# AntiAlias_Filter_Diff_Active.net
KiCad netlist of a schematic drawn in EAGLE
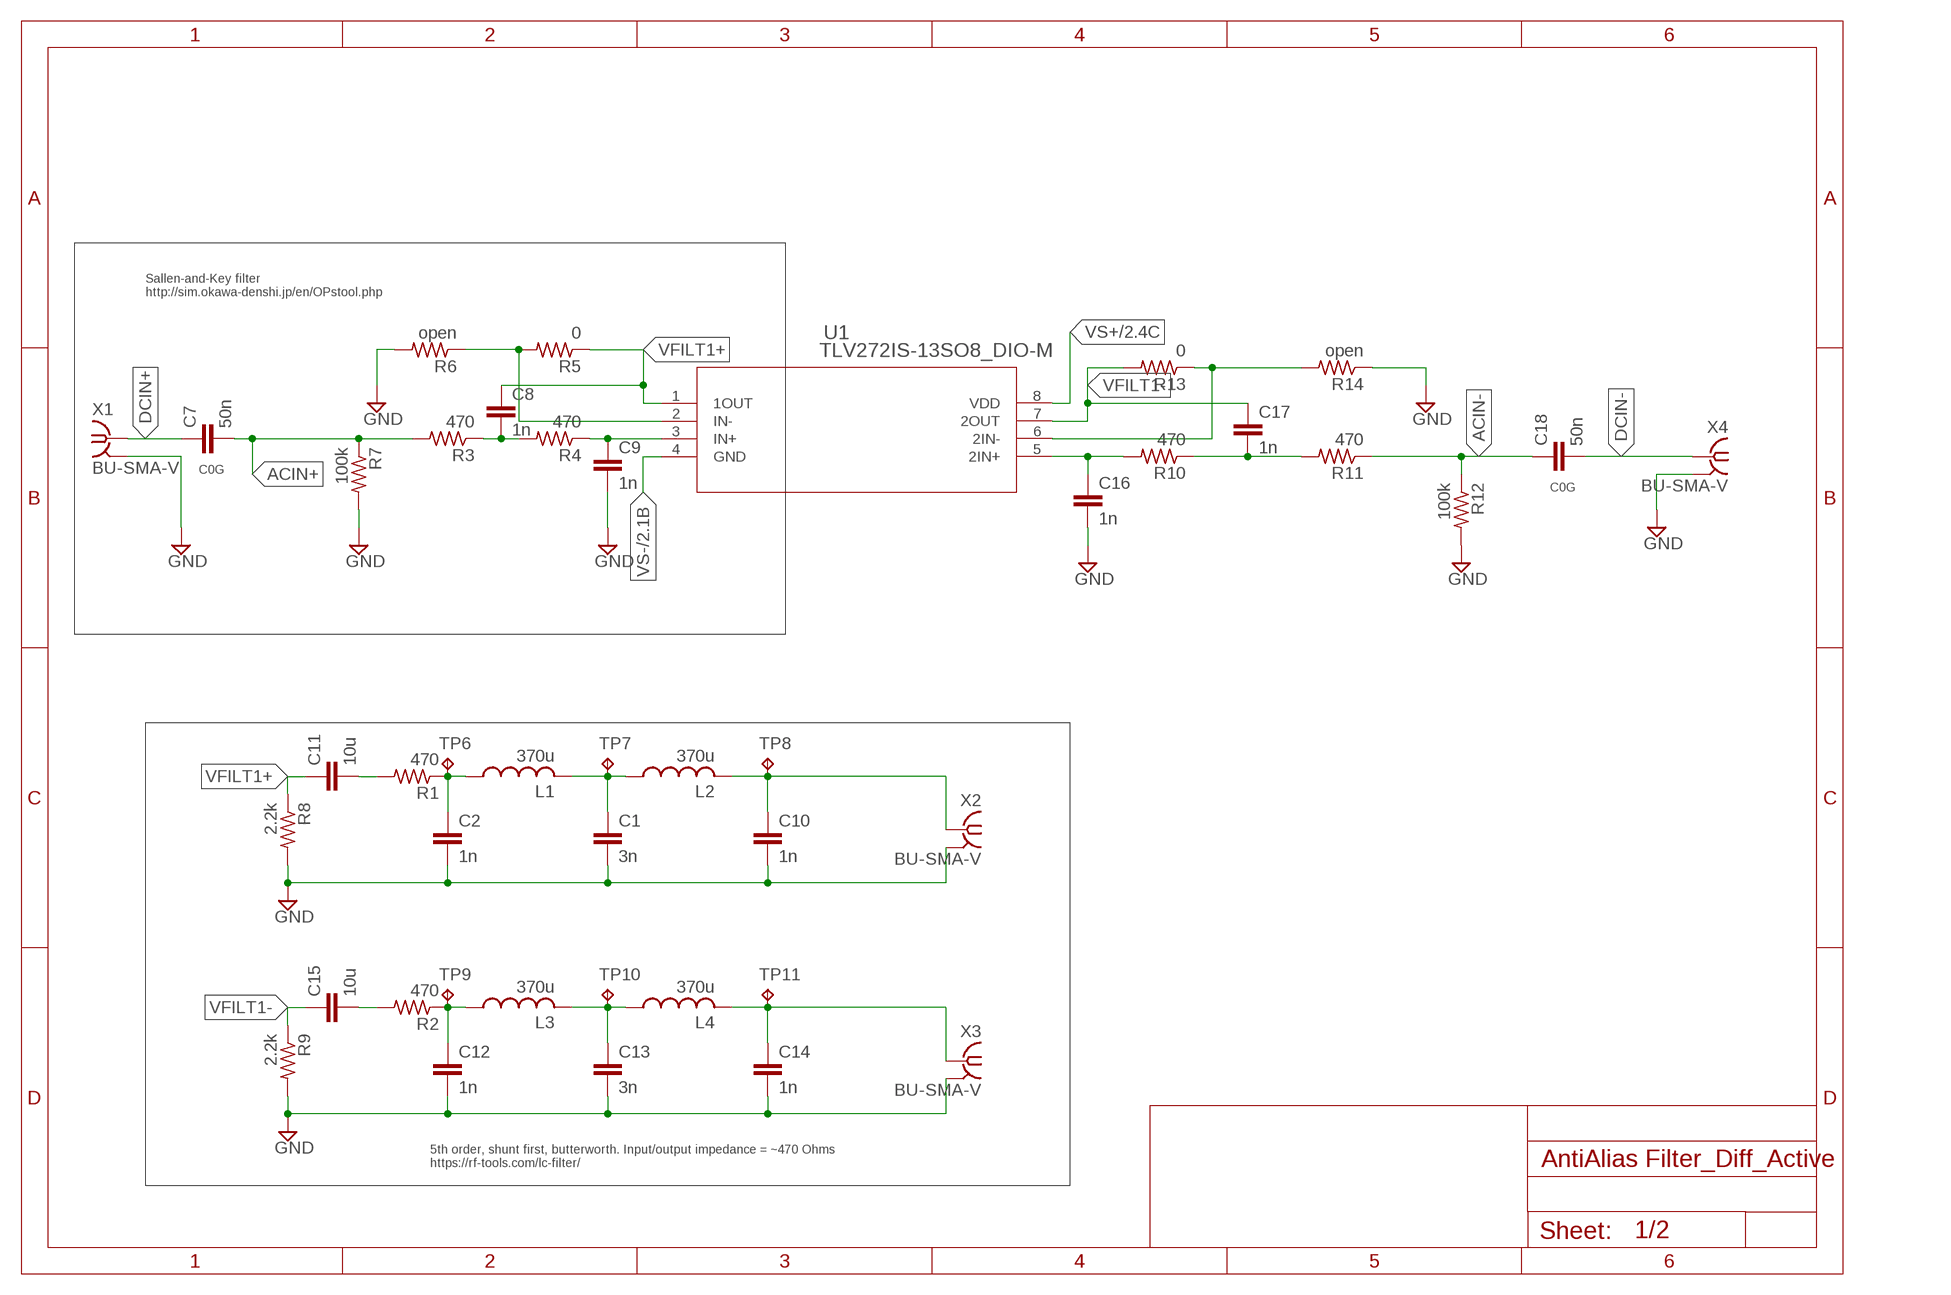
[diagram p0: schematic, sheet 1]
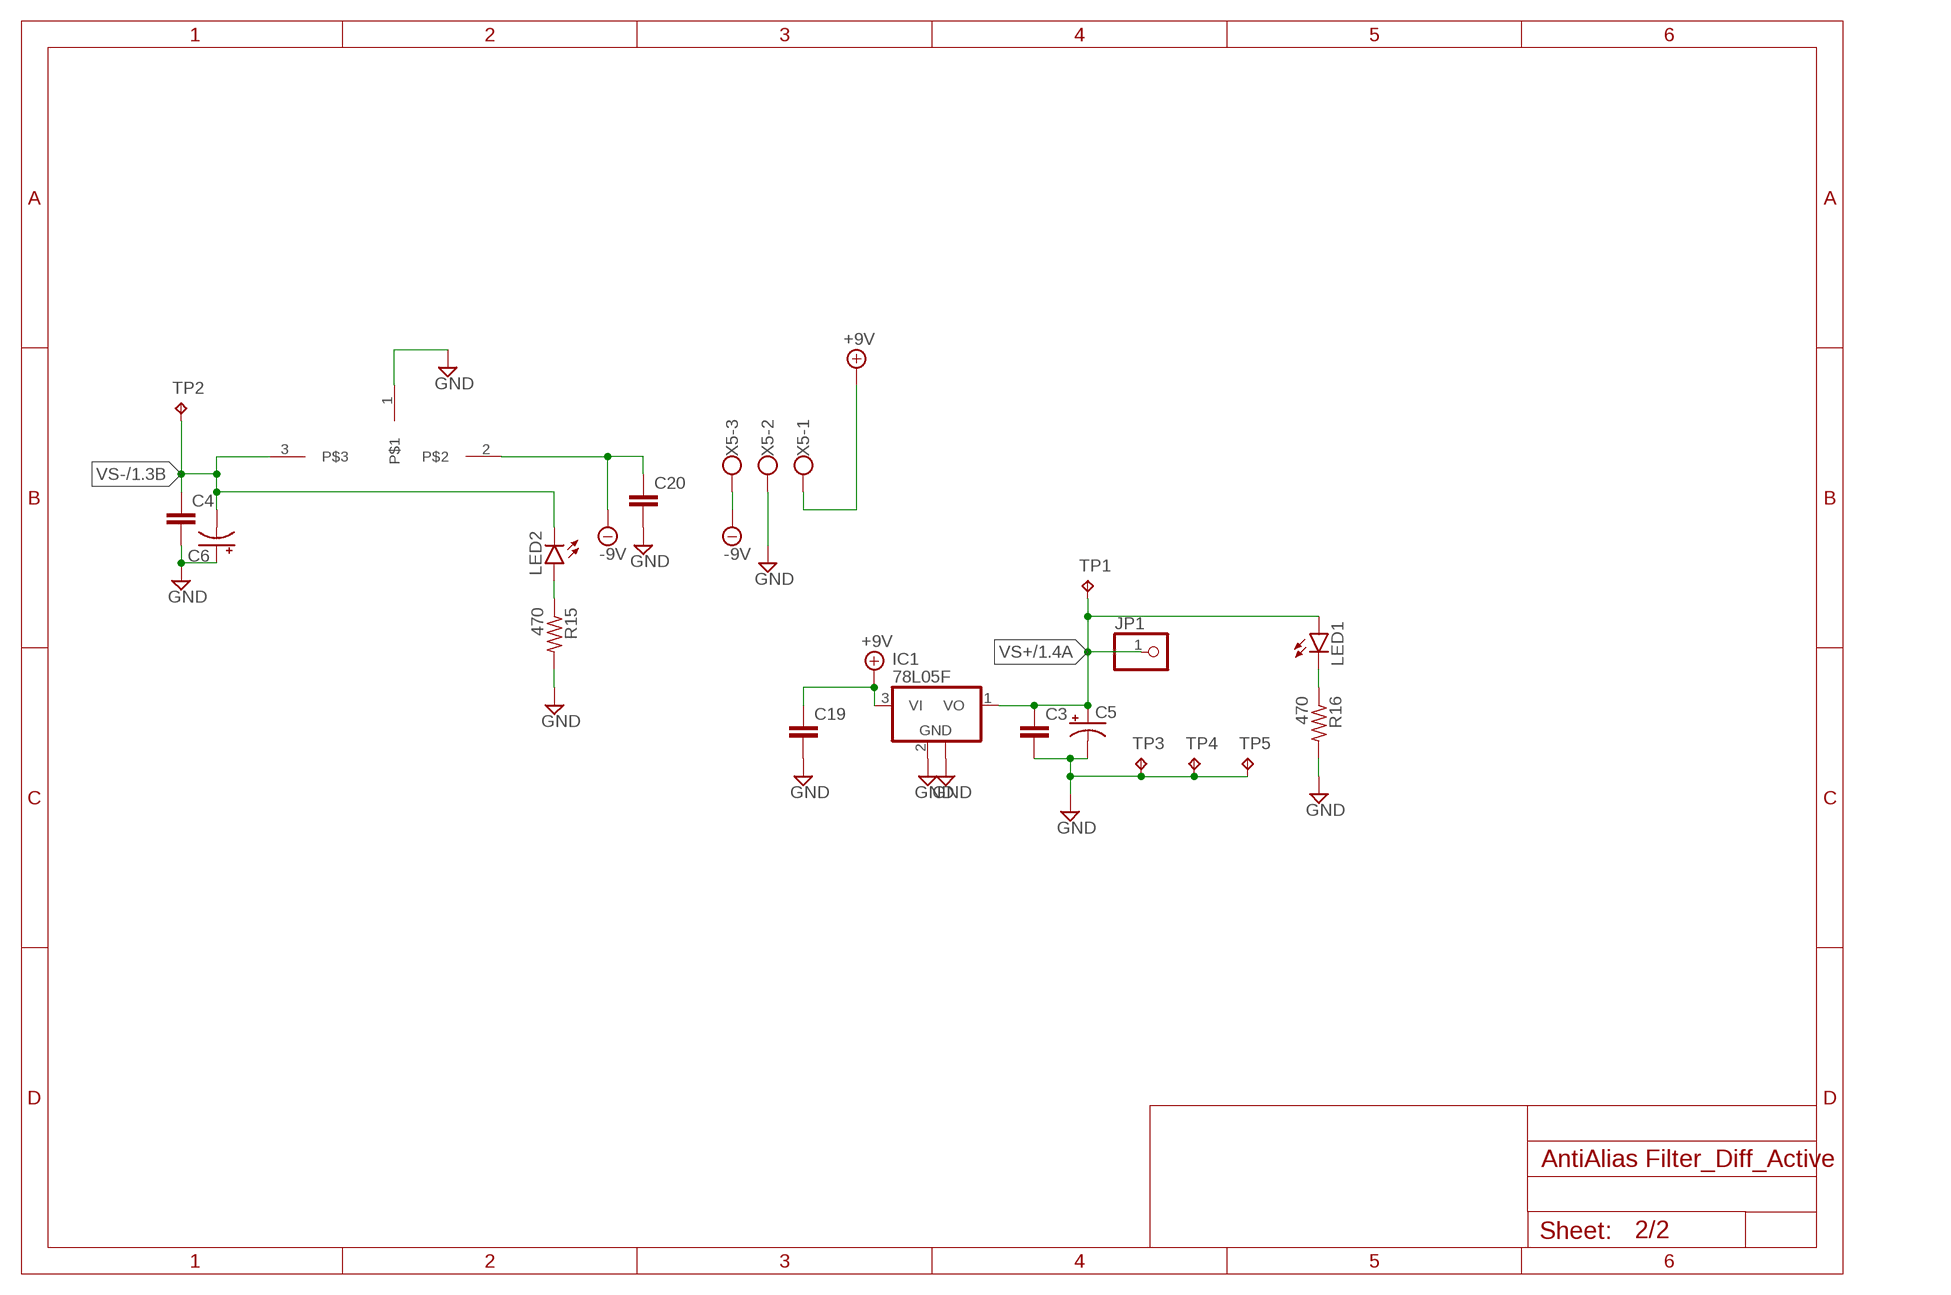
[diagram p1: schematic, sheet 2]

(export (version "E")
  (design (tool "Eeschema 10.0.6"))
  (components
    (comp (ref "C3")
      (value "C-EUC1206")
      (footprint "eagle-import:C1206")
      (libsource (lib "eagle-import") (part "C-EUC1206"))
    )
    (comp (ref "C4")
      (value "C-EUC1206")
      (footprint "eagle-import:C1206")
      (libsource (lib "eagle-import") (part "C-EUC1206"))
    )
    (comp (ref "C5")
      (value "CPOL-USE2.5-5")
      (footprint "eagle-import:E2,5-5")
      (libsource (lib "eagle-import") (part "CPOL-USE2.5-5"))
    )
    (comp (ref "C6")
      (value "CPOL-USE2.5-5")
      (footprint "eagle-import:E2,5-5")
      (libsource (lib "eagle-import") (part "CPOL-USE2.5-5"))
    )
    (comp (ref "C19")
      (value "C-EUC1206")
      (footprint "eagle-import:C1206")
      (libsource (lib "eagle-import") (part "C-EUC1206"))
    )
    (comp (ref "C20")
      (value "C-EUC1206")
      (footprint "eagle-import:C1206")
      (libsource (lib "eagle-import") (part "C-EUC1206"))
    )
    (comp (ref "IC1")
      (value "78L05F")
      (footprint "eagle-import:SOT89")
      (libsource (lib "eagle-import") (part "78LF05"))
    )
    (comp (ref "JP1")
      (value "PINHD-1X1")
      (footprint "eagle-import:1X01")
      (libsource (lib "eagle-import") (part "PINHD-1X1"))
    )
    (comp (ref "LED1")
      (value "LEDCHIPLED_1206")
      (footprint "eagle-import:CHIPLED_1206")
      (libsource (lib "eagle-import") (part "LEDCHIPLED_1206"))
    )
    (comp (ref "LED2")
      (value "LEDCHIPLED_1206")
      (footprint "eagle-import:CHIPLED_1206")
      (libsource (lib "eagle-import") (part "LEDCHIPLED_1206"))
    )
    (comp (ref "R15")
      (value "470")
      (footprint "eagle-import:R1206")
      (libsource (lib "eagle-import") (part "R-US_R1206"))
    )
    (comp (ref "R16")
      (value "470")
      (footprint "eagle-import:R1206")
      (libsource (lib "eagle-import") (part "R-US_R1206"))
    )
    (comp (ref "TP1")
      (value "TPTP20SQ")
      (footprint "eagle-import:TP20SQ")
      (libsource (lib "eagle-import") (part "TPTP20SQ"))
    )
    (comp (ref "TP2")
      (value "TPTP20SQ")
      (footprint "eagle-import:TP20SQ")
      (libsource (lib "eagle-import") (part "TPTP20SQ"))
    )
    (comp (ref "TP3")
      (value "TPTP20SQ")
      (footprint "eagle-import:TP20SQ")
      (libsource (lib "eagle-import") (part "TPTP20SQ"))
    )
    (comp (ref "TP4")
      (value "TPTP20SQ")
      (footprint "eagle-import:TP20SQ")
      (libsource (lib "eagle-import") (part "TPTP20SQ"))
    )
    (comp (ref "TP5")
      (value "TPTP20SQ")
      (footprint "eagle-import:TP20SQ")
      (libsource (lib "eagle-import") (part "TPTP20SQ"))
    )
    (comp (ref "U$1")
      (value "79LXX")
      (footprint "eagle-import:VREG_L78L12ABUTR")
      (libsource (lib "eagle-import") (part "79LXX"))
    )
    (comp (ref "X5")
      (value "W237-103")
      (footprint "eagle-import:W237-103")
      (fields (field (name "MPN") "237-103"))
      (libsource (lib "eagle-import") (part "W237-103"))
    )
    (comp (ref "C1")
      (value "3n")
      (footprint "eagle-import:C1206")
      (libsource (lib "eagle-import") (part "C-EUC1206"))
    )
    (comp (ref "C2")
      (value "1n")
      (footprint "eagle-import:C1206")
      (libsource (lib "eagle-import") (part "C-EUC1206"))
    )
    (comp (ref "C7")
      (value "50n")
      (footprint "eagle-import:C1210")
      (libsource (lib "eagle-import") (part "C-EUC1210"))
    )
    (comp (ref "C8")
      (value "1n")
      (footprint "eagle-import:C1206")
      (libsource (lib "eagle-import") (part "C-EUC1206"))
    )
    (comp (ref "C9")
      (value "1n")
      (footprint "eagle-import:C1206")
      (libsource (lib "eagle-import") (part "C-EUC1206"))
    )
    (comp (ref "C10")
      (value "1n")
      (footprint "eagle-import:C1206")
      (libsource (lib "eagle-import") (part "C-EUC1206"))
    )
    (comp (ref "C11")
      (value "10u")
      (footprint "eagle-import:C1210")
      (libsource (lib "eagle-import") (part "C-EUC1210"))
    )
    (comp (ref "C12")
      (value "1n")
      (footprint "eagle-import:C1206")
      (libsource (lib "eagle-import") (part "C-EUC1206"))
    )
    (comp (ref "C13")
      (value "3n")
      (footprint "eagle-import:C1206")
      (libsource (lib "eagle-import") (part "C-EUC1206"))
    )
    (comp (ref "C14")
      (value "1n")
      (footprint "eagle-import:C1206")
      (libsource (lib "eagle-import") (part "C-EUC1206"))
    )
    (comp (ref "C15")
      (value "10u")
      (footprint "eagle-import:C1210")
      (libsource (lib "eagle-import") (part "C-EUC1210"))
    )
    (comp (ref "C16")
      (value "1n")
      (footprint "eagle-import:C1206")
      (libsource (lib "eagle-import") (part "C-EUC1206"))
    )
    (comp (ref "C17")
      (value "1n")
      (footprint "eagle-import:C1206")
      (libsource (lib "eagle-import") (part "C-EUC1206"))
    )
    (comp (ref "C18")
      (value "50n")
      (footprint "eagle-import:C1210")
      (libsource (lib "eagle-import") (part "C-EUC1210"))
    )
    (comp (ref "L1")
      (value "370u")
      (footprint "eagle-import:L1812")
      (libsource (lib "eagle-import") (part "L-USL1812"))
    )
    (comp (ref "L2")
      (value "370u")
      (footprint "eagle-import:L1812")
      (libsource (lib "eagle-import") (part "L-USL1812"))
    )
    (comp (ref "L3")
      (value "370u")
      (footprint "eagle-import:L1812")
      (libsource (lib "eagle-import") (part "L-USL1812"))
    )
    (comp (ref "L4")
      (value "370u")
      (footprint "eagle-import:L1812")
      (libsource (lib "eagle-import") (part "L-USL1812"))
    )
    (comp (ref "R1")
      (value "470")
      (footprint "eagle-import:R1206")
      (libsource (lib "eagle-import") (part "R-US_R1206"))
    )
    (comp (ref "R2")
      (value "470")
      (footprint "eagle-import:R1206")
      (libsource (lib "eagle-import") (part "R-US_R1206"))
    )
    (comp (ref "R3")
      (value "470")
      (footprint "eagle-import:R1206")
      (libsource (lib "eagle-import") (part "R-US_R1206"))
    )
    (comp (ref "R4")
      (value "470")
      (footprint "eagle-import:R1206")
      (libsource (lib "eagle-import") (part "R-US_R1206"))
    )
    (comp (ref "R5")
      (value "0")
      (footprint "eagle-import:R1206")
      (libsource (lib "eagle-import") (part "R-US_R1206"))
    )
    (comp (ref "R6")
      (value "open")
      (footprint "eagle-import:R1206")
      (libsource (lib "eagle-import") (part "R-US_R1206"))
    )
    (comp (ref "R7")
      (value "100k")
      (footprint "eagle-import:R1206")
      (libsource (lib "eagle-import") (part "R-US_R1206"))
    )
    (comp (ref "R8")
      (value "2.2k")
      (footprint "eagle-import:R1206")
      (libsource (lib "eagle-import") (part "R-US_R1206"))
    )
    (comp (ref "R9")
      (value "2.2k")
      (footprint "eagle-import:R1206")
      (libsource (lib "eagle-import") (part "R-US_R1206"))
    )
    (comp (ref "R10")
      (value "470")
      (footprint "eagle-import:R1206")
      (libsource (lib "eagle-import") (part "R-US_R1206"))
    )
    (comp (ref "R11")
      (value "470")
      (footprint "eagle-import:R1206")
      (libsource (lib "eagle-import") (part "R-US_R1206"))
    )
    (comp (ref "R12")
      (value "100k")
      (footprint "eagle-import:R1206")
      (libsource (lib "eagle-import") (part "R-US_R1206"))
    )
    (comp (ref "R13")
      (value "0")
      (footprint "eagle-import:R1206")
      (libsource (lib "eagle-import") (part "R-US_R1206"))
    )
    (comp (ref "R14")
      (value "open")
      (footprint "eagle-import:R1206")
      (libsource (lib "eagle-import") (part "R-US_R1206"))
    )
    (comp (ref "TP6")
      (value "TPTP20SQ")
      (footprint "eagle-import:TP20SQ")
      (libsource (lib "eagle-import") (part "TPTP20SQ"))
    )
    (comp (ref "TP7")
      (value "TPTP20SQ")
      (footprint "eagle-import:TP20SQ")
      (libsource (lib "eagle-import") (part "TPTP20SQ"))
    )
    (comp (ref "TP8")
      (value "TPTP20SQ")
      (footprint "eagle-import:TP20SQ")
      (libsource (lib "eagle-import") (part "TPTP20SQ"))
    )
    (comp (ref "TP9")
      (value "TPTP20SQ")
      (footprint "eagle-import:TP20SQ")
      (libsource (lib "eagle-import") (part "TPTP20SQ"))
    )
    (comp (ref "TP10")
      (value "TPTP20SQ")
      (footprint "eagle-import:TP20SQ")
      (libsource (lib "eagle-import") (part "TPTP20SQ"))
    )
    (comp (ref "TP11")
      (value "TPTP20SQ")
      (footprint "eagle-import:TP20SQ")
      (libsource (lib "eagle-import") (part "TPTP20SQ"))
    )
    (comp (ref "U1")
      (value "TLV272IS-13SO8_DIO-M")
      (footprint "eagle-import:SO8_DIO-M")
      (fields (field (name "MANUFACTURER_PART_NUMBER") "TLV272IS-13"))
      (libsource (lib "eagle-import") (part "TLV272IS-13SO8_DIO-M"))
    )
    (comp (ref "X1")
      (value "BU-SMA-V")
      (footprint "eagle-import:BU-SMA-V")
      (libsource (lib "eagle-import") (part "BU-SMA-V"))
    )
    (comp (ref "X2")
      (value "BU-SMA-V")
      (footprint "eagle-import:BU-SMA-V")
      (libsource (lib "eagle-import") (part "BU-SMA-V"))
    )
    (comp (ref "X3")
      (value "BU-SMA-V")
      (footprint "eagle-import:BU-SMA-V")
      (libsource (lib "eagle-import") (part "BU-SMA-V"))
    )
    (comp (ref "X4")
      (value "BU-SMA-V")
      (footprint "eagle-import:BU-SMA-V")
      (libsource (lib "eagle-import") (part "BU-SMA-V"))
    )
  )
  (nets
    (net (code "1") (name "+9V") (class "Default")
      (node (ref "C19") (pin "1") (pinfunction "1_1") (pintype "passive"))
      (node (ref "IC1") (pin "3") (pinfunction "VI_3") (pintype "input"))
      (node (ref "X5") (pin "1") (pinfunction "KL_1") (pintype "passive"))
    )
    (net (code "2") (name "-9V") (class "Default")
      (node (ref "C20") (pin "1") (pinfunction "1_1") (pintype "passive"))
      (node (ref "U$1") (pin "2") (pinfunction "P$2_2") (pintype "bidirectional"))
      (node (ref "X5") (pin "3") (pinfunction "KL_3") (pintype "passive"))
    )
    (net (code "3") (name "ACIN+") (class "Default")
      (node (ref "C7") (pin "2") (pinfunction "2_2") (pintype "passive"))
      (node (ref "R3") (pin "2") (pinfunction "2_2") (pintype "passive"))
      (node (ref "R7") (pin "1") (pinfunction "1_1") (pintype "passive"))
    )
    (net (code "4") (name "ACIN-") (class "Default")
      (node (ref "C18") (pin "1") (pinfunction "1_1") (pintype "passive"))
      (node (ref "R11") (pin "1") (pinfunction "1_1") (pintype "passive"))
      (node (ref "R12") (pin "1") (pinfunction "1_1") (pintype "passive"))
    )
    (net (code "5") (name "DCIN+") (class "Default")
      (node (ref "C7") (pin "1") (pinfunction "1_1") (pintype "passive"))
      (node (ref "X1") (pin "1") (pinfunction "1_1") (pintype "passive"))
    )
    (net (code "6") (name "DCIN-") (class "Default")
      (node (ref "C18") (pin "2") (pinfunction "2_2") (pintype "passive"))
      (node (ref "X4") (pin "1") (pinfunction "1_1") (pintype "passive"))
    )
    (net (code "7") (name "GND") (class "Default")
      (node (ref "C1") (pin "2") (pinfunction "2_2") (pintype "passive"))
      (node (ref "C10") (pin "2") (pinfunction "2_2") (pintype "passive"))
      (node (ref "C12") (pin "2") (pinfunction "2_2") (pintype "passive"))
      (node (ref "C13") (pin "2") (pinfunction "2_2") (pintype "passive"))
      (node (ref "C14") (pin "2") (pinfunction "2_2") (pintype "passive"))
      (node (ref "C16") (pin "2") (pinfunction "2_2") (pintype "passive"))
      (node (ref "C19") (pin "2") (pinfunction "2_2") (pintype "passive"))
      (node (ref "C2") (pin "2") (pinfunction "2_2") (pintype "passive"))
      (node (ref "C20") (pin "2") (pinfunction "2_2") (pintype "passive"))
      (node (ref "C3") (pin "2") (pinfunction "2_2") (pintype "passive"))
      (node (ref "C4") (pin "2") (pinfunction "2_2") (pintype "passive"))
      (node (ref "C5") (pin "-") (pinfunction "-_-") (pintype "passive"))
      (node (ref "C6") (pin "+") (pinfunction "+_+") (pintype "passive"))
      (node (ref "C9") (pin "2") (pinfunction "2_2") (pintype "passive"))
      (node (ref "IC1") (pin "2") (pinfunction "GND_2") (pintype "passive"))
      (node (ref "IC1") (pin "2@1") (pinfunction "GND_2@1") (pintype "passive"))
      (node (ref "R12") (pin "2") (pinfunction "2_2") (pintype "passive"))
      (node (ref "R14") (pin "1") (pinfunction "1_1") (pintype "passive"))
      (node (ref "R15") (pin "2") (pinfunction "2_2") (pintype "passive"))
      (node (ref "R16") (pin "2") (pinfunction "2_2") (pintype "passive"))
      (node (ref "R6") (pin "2") (pinfunction "2_2") (pintype "passive"))
      (node (ref "R7") (pin "2") (pinfunction "2_2") (pintype "passive"))
      (node (ref "R8") (pin "2") (pinfunction "2_2") (pintype "passive"))
      (node (ref "R9") (pin "2") (pinfunction "2_2") (pintype "passive"))
      (node (ref "TP3") (pin "TP") (pinfunction "TP_TP") (pintype "input"))
      (node (ref "TP4") (pin "TP") (pinfunction "TP_TP") (pintype "input"))
      (node (ref "TP5") (pin "TP") (pinfunction "TP_TP") (pintype "input"))
      (node (ref "U$1") (pin "1") (pinfunction "P$1_1") (pintype "bidirectional"))
      (node (ref "X1") (pin "2") (pinfunction "2_2") (pintype "passive"))
      (node (ref "X1") (pin "3") (pinfunction "2_3") (pintype "passive"))
      (node (ref "X1") (pin "4") (pinfunction "2_4") (pintype "passive"))
      (node (ref "X1") (pin "5") (pinfunction "2_5") (pintype "passive"))
      (node (ref "X2") (pin "2") (pinfunction "2_2") (pintype "passive"))
      (node (ref "X2") (pin "3") (pinfunction "2_3") (pintype "passive"))
      (node (ref "X2") (pin "4") (pinfunction "2_4") (pintype "passive"))
      (node (ref "X2") (pin "5") (pinfunction "2_5") (pintype "passive"))
      (node (ref "X3") (pin "2") (pinfunction "2_2") (pintype "passive"))
      (node (ref "X3") (pin "3") (pinfunction "2_3") (pintype "passive"))
      (node (ref "X3") (pin "4") (pinfunction "2_4") (pintype "passive"))
      (node (ref "X3") (pin "5") (pinfunction "2_5") (pintype "passive"))
      (node (ref "X4") (pin "2") (pinfunction "2_2") (pintype "passive"))
      (node (ref "X4") (pin "3") (pinfunction "2_3") (pintype "passive"))
      (node (ref "X4") (pin "4") (pinfunction "2_4") (pintype "passive"))
      (node (ref "X4") (pin "5") (pinfunction "2_5") (pintype "passive"))
      (node (ref "X5") (pin "2") (pinfunction "KL_2") (pintype "passive"))
    )
    (net (code "8") (name "Net-(C1-Pad1)") (class "Default")
      (node (ref "C1") (pin "1") (pinfunction "1_1") (pintype "passive"))
      (node (ref "L1") (pin "2") (pinfunction "2_2") (pintype "passive"))
      (node (ref "L2") (pin "1") (pinfunction "1_1") (pintype "passive"))
      (node (ref "TP7") (pin "TP") (pinfunction "TP_TP") (pintype "input"))
    )
    (net (code "9") (name "Net-(C2-Pad1)") (class "Default")
      (node (ref "C2") (pin "1") (pinfunction "1_1") (pintype "passive"))
      (node (ref "L1") (pin "1") (pinfunction "1_1") (pintype "passive"))
      (node (ref "R1") (pin "1") (pinfunction "1_1") (pintype "passive"))
      (node (ref "TP6") (pin "TP") (pinfunction "TP_TP") (pintype "input"))
    )
    (net (code "10") (name "Net-(C8-Pad2)") (class "Default")
      (node (ref "C8") (pin "2") (pinfunction "2_2") (pintype "passive"))
      (node (ref "R3") (pin "1") (pinfunction "1_1") (pintype "passive"))
      (node (ref "R4") (pin "2") (pinfunction "2_2") (pintype "passive"))
    )
    (net (code "11") (name "Net-(C10-Pad1)") (class "Default")
      (node (ref "C10") (pin "1") (pinfunction "1_1") (pintype "passive"))
      (node (ref "L2") (pin "2") (pinfunction "2_2") (pintype "passive"))
      (node (ref "TP8") (pin "TP") (pinfunction "TP_TP") (pintype "input"))
      (node (ref "X2") (pin "1") (pinfunction "1_1") (pintype "passive"))
    )
    (net (code "12") (name "Net-(C11-Pad2)") (class "Default")
      (node (ref "C11") (pin "2") (pinfunction "2_2") (pintype "passive"))
      (node (ref "R1") (pin "2") (pinfunction "2_2") (pintype "passive"))
    )
    (net (code "13") (name "Net-(C12-Pad1)") (class "Default")
      (node (ref "C12") (pin "1") (pinfunction "1_1") (pintype "passive"))
      (node (ref "L3") (pin "1") (pinfunction "1_1") (pintype "passive"))
      (node (ref "R2") (pin "1") (pinfunction "1_1") (pintype "passive"))
      (node (ref "TP9") (pin "TP") (pinfunction "TP_TP") (pintype "input"))
    )
    (net (code "14") (name "Net-(C13-Pad1)") (class "Default")
      (node (ref "C13") (pin "1") (pinfunction "1_1") (pintype "passive"))
      (node (ref "L3") (pin "2") (pinfunction "2_2") (pintype "passive"))
      (node (ref "L4") (pin "1") (pinfunction "1_1") (pintype "passive"))
      (node (ref "TP10") (pin "TP") (pinfunction "TP_TP") (pintype "input"))
    )
    (net (code "15") (name "Net-(C14-Pad1)") (class "Default")
      (node (ref "C14") (pin "1") (pinfunction "1_1") (pintype "passive"))
      (node (ref "L4") (pin "2") (pinfunction "2_2") (pintype "passive"))
      (node (ref "TP11") (pin "TP") (pinfunction "TP_TP") (pintype "input"))
      (node (ref "X3") (pin "1") (pinfunction "1_1") (pintype "passive"))
    )
    (net (code "16") (name "Net-(C15-Pad2)") (class "Default")
      (node (ref "C15") (pin "2") (pinfunction "2_2") (pintype "passive"))
      (node (ref "R2") (pin "2") (pinfunction "2_2") (pintype "passive"))
    )
    (net (code "17") (name "Net-(C17-Pad2)") (class "Default")
      (node (ref "C17") (pin "2") (pinfunction "2_2") (pintype "passive"))
      (node (ref "R10") (pin "1") (pinfunction "1_1") (pintype "passive"))
      (node (ref "R11") (pin "2") (pinfunction "2_2") (pintype "passive"))
    )
    (net (code "18") (name "Net-(LED1-PadC)") (class "Default")
      (node (ref "LED1") (pin "C") (pinfunction "C_C") (pintype "passive"))
      (node (ref "R16") (pin "1") (pinfunction "1_1") (pintype "passive"))
    )
    (net (code "19") (name "Net-(LED2-PadA)") (class "Default")
      (node (ref "LED2") (pin "A") (pinfunction "A_A") (pintype "passive"))
      (node (ref "R15") (pin "1") (pinfunction "1_1") (pintype "passive"))
    )
    (net (code "20") (name "Net-(U1-2IN+)") (class "Default")
      (node (ref "C16") (pin "1") (pinfunction "1_1") (pintype "passive"))
      (node (ref "R10") (pin "2") (pinfunction "2_2") (pintype "passive"))
      (node (ref "U1") (pin "5") (pinfunction "2IN+_5") (pintype "input"))
    )
    (net (code "21") (name "Net-(U1-2IN-)") (class "Default")
      (node (ref "R13") (pin "1") (pinfunction "1_1") (pintype "passive"))
      (node (ref "R14") (pin "2") (pinfunction "2_2") (pintype "passive"))
      (node (ref "U1") (pin "6") (pinfunction "2IN-_6") (pintype "input"))
    )
    (net (code "22") (name "Net-(U1-IN+)") (class "Default")
      (node (ref "C9") (pin "1") (pinfunction "1_1") (pintype "passive"))
      (node (ref "R4") (pin "1") (pinfunction "1_1") (pintype "passive"))
      (node (ref "U1") (pin "3") (pinfunction "IN+_3") (pintype "input"))
    )
    (net (code "23") (name "Net-(U1-IN-)") (class "Default")
      (node (ref "R5") (pin "2") (pinfunction "2_2") (pintype "passive"))
      (node (ref "R6") (pin "1") (pinfunction "1_1") (pintype "passive"))
      (node (ref "U1") (pin "2") (pinfunction "IN-_2") (pintype "input"))
    )
    (net (code "24") (name "VFILT1+") (class "Default")
      (node (ref "C11") (pin "1") (pinfunction "1_1") (pintype "passive"))
      (node (ref "C8") (pin "1") (pinfunction "1_1") (pintype "passive"))
      (node (ref "R5") (pin "1") (pinfunction "1_1") (pintype "passive"))
      (node (ref "R8") (pin "1") (pinfunction "1_1") (pintype "passive"))
      (node (ref "U1") (pin "1") (pinfunction "1OUT_1") (pintype "output"))
    )
    (net (code "25") (name "VFILT1-") (class "Default")
      (node (ref "C15") (pin "1") (pinfunction "1_1") (pintype "passive"))
      (node (ref "C17") (pin "1") (pinfunction "1_1") (pintype "passive"))
      (node (ref "R13") (pin "2") (pinfunction "2_2") (pintype "passive"))
      (node (ref "R9") (pin "1") (pinfunction "1_1") (pintype "passive"))
      (node (ref "U1") (pin "7") (pinfunction "2OUT_7") (pintype "output"))
    )
    (net (code "26") (name "VS+") (class "Default")
      (node (ref "C3") (pin "1") (pinfunction "1_1") (pintype "passive"))
      (node (ref "C5") (pin "+") (pinfunction "+_+") (pintype "passive"))
      (node (ref "IC1") (pin "1") (pinfunction "VO_1") (pintype "passive"))
      (node (ref "JP1") (pin "1") (pinfunction "1_1") (pintype "passive"))
      (node (ref "LED1") (pin "A") (pinfunction "A_A") (pintype "passive"))
      (node (ref "TP1") (pin "TP") (pinfunction "TP_TP") (pintype "input"))
      (node (ref "U1") (pin "8") (pinfunction "VDD_8") (pintype "power_in"))
    )
    (net (code "27") (name "VS-") (class "Default")
      (node (ref "C4") (pin "1") (pinfunction "1_1") (pintype "passive"))
      (node (ref "C6") (pin "-") (pinfunction "-_-") (pintype "passive"))
      (node (ref "LED2") (pin "C") (pinfunction "C_C") (pintype "passive"))
      (node (ref "TP2") (pin "TP") (pinfunction "TP_TP") (pintype "input"))
      (node (ref "U$1") (pin "3") (pinfunction "P$3_3") (pintype "bidirectional"))
      (node (ref "U1") (pin "4") (pinfunction "GND_4") (pintype "power_in"))
    )
  )
)
